# LPDDR4X_Ground.net
KiCad netlist of a schematic drawn in Altium Designer
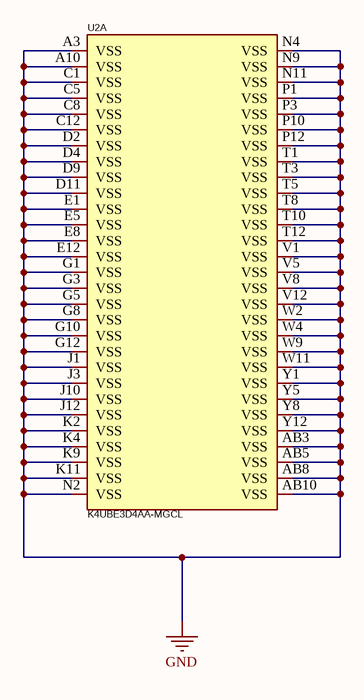
[diagram p0: LPDDR4X_Ground.SchDoc]

(export (version "E")
  (design (tool "Eeschema 10.0.6"))
  (components
    (comp (ref "U2")
      (value "K4UBE3D4AA-MGCL")
      (footprint "K4F8E304HB-MGCJ")
      (fields (field (name "MANUFACTURER") "SAMSUNG(三星半导体)"))
      (libsource (lib "kit") (part "K4UBE3D4AA-MGCL"))
    )
  )
  (nets
    (net (code "1") (name "GND") (class "Default")
      (node (ref "U2") (pin "A10") (pinfunction "VSS_A10") (pintype "passive"))
      (node (ref "U2") (pin "A3") (pinfunction "VSS_A3") (pintype "passive"))
      (node (ref "U2") (pin "AB10") (pinfunction "VSS_AB10") (pintype "passive"))
      (node (ref "U2") (pin "AB3") (pinfunction "VSS_AB3") (pintype "passive"))
      (node (ref "U2") (pin "AB5") (pinfunction "VSS_AB5") (pintype "passive"))
      (node (ref "U2") (pin "AB8") (pinfunction "VSS_AB8") (pintype "passive"))
      (node (ref "U2") (pin "C1") (pinfunction "VSS_C1") (pintype "passive"))
      (node (ref "U2") (pin "C12") (pinfunction "VSS_C12") (pintype "passive"))
      (node (ref "U2") (pin "C5") (pinfunction "VSS_C5") (pintype "passive"))
      (node (ref "U2") (pin "C8") (pinfunction "VSS_C8") (pintype "passive"))
      (node (ref "U2") (pin "D11") (pinfunction "VSS_D11") (pintype "passive"))
      (node (ref "U2") (pin "D2") (pinfunction "VSS_D2") (pintype "passive"))
      (node (ref "U2") (pin "D4") (pinfunction "VSS_D4") (pintype "passive"))
      (node (ref "U2") (pin "D9") (pinfunction "VSS_D9") (pintype "passive"))
      (node (ref "U2") (pin "E1") (pinfunction "VSS_E1") (pintype "passive"))
      (node (ref "U2") (pin "E12") (pinfunction "VSS_E12") (pintype "passive"))
      (node (ref "U2") (pin "E5") (pinfunction "VSS_E5") (pintype "passive"))
      (node (ref "U2") (pin "E8") (pinfunction "VSS_E8") (pintype "passive"))
      (node (ref "U2") (pin "G1") (pinfunction "VSS_G1") (pintype "passive"))
      (node (ref "U2") (pin "G10") (pinfunction "VSS_G10") (pintype "passive"))
      (node (ref "U2") (pin "G12") (pinfunction "VSS_G12") (pintype "passive"))
      (node (ref "U2") (pin "G3") (pinfunction "VSS_G3") (pintype "passive"))
      (node (ref "U2") (pin "G5") (pinfunction "VSS_G5") (pintype "passive"))
      (node (ref "U2") (pin "G8") (pinfunction "VSS_G8") (pintype "passive"))
      (node (ref "U2") (pin "J1") (pinfunction "VSS_J1") (pintype "passive"))
      (node (ref "U2") (pin "J10") (pinfunction "VSS_J10") (pintype "passive"))
      (node (ref "U2") (pin "J12") (pinfunction "VSS_J12") (pintype "passive"))
      (node (ref "U2") (pin "J3") (pinfunction "VSS_J3") (pintype "passive"))
      (node (ref "U2") (pin "K11") (pinfunction "VSS_K11") (pintype "passive"))
      (node (ref "U2") (pin "K2") (pinfunction "VSS_K2") (pintype "passive"))
      (node (ref "U2") (pin "K4") (pinfunction "VSS_K4") (pintype "passive"))
      (node (ref "U2") (pin "K9") (pinfunction "VSS_K9") (pintype "passive"))
      (node (ref "U2") (pin "N11") (pinfunction "VSS_N11") (pintype "passive"))
      (node (ref "U2") (pin "N2") (pinfunction "VSS_N2") (pintype "passive"))
      (node (ref "U2") (pin "N4") (pinfunction "VSS_N4") (pintype "passive"))
      (node (ref "U2") (pin "N9") (pinfunction "VSS_N9") (pintype "passive"))
      (node (ref "U2") (pin "P1") (pinfunction "VSS_P1") (pintype "passive"))
      (node (ref "U2") (pin "P10") (pinfunction "VSS_P10") (pintype "passive"))
      (node (ref "U2") (pin "P12") (pinfunction "VSS_P12") (pintype "passive"))
      (node (ref "U2") (pin "P3") (pinfunction "VSS_P3") (pintype "passive"))
      (node (ref "U2") (pin "T1") (pinfunction "VSS_T1") (pintype "passive"))
      (node (ref "U2") (pin "T10") (pinfunction "VSS_T10") (pintype "passive"))
      (node (ref "U2") (pin "T12") (pinfunction "VSS_T12") (pintype "passive"))
      (node (ref "U2") (pin "T3") (pinfunction "VSS_T3") (pintype "passive"))
      (node (ref "U2") (pin "T5") (pinfunction "VSS_T5") (pintype "passive"))
      (node (ref "U2") (pin "T8") (pinfunction "VSS_T8") (pintype "passive"))
      (node (ref "U2") (pin "V1") (pinfunction "VSS_V1") (pintype "passive"))
      (node (ref "U2") (pin "V12") (pinfunction "VSS_V12") (pintype "passive"))
      (node (ref "U2") (pin "V5") (pinfunction "VSS_V5") (pintype "passive"))
      (node (ref "U2") (pin "V8") (pinfunction "VSS_V8") (pintype "passive"))
      (node (ref "U2") (pin "W11") (pinfunction "VSS_W11") (pintype "passive"))
      (node (ref "U2") (pin "W2") (pinfunction "VSS_W2") (pintype "passive"))
      (node (ref "U2") (pin "W4") (pinfunction "VSS_W4") (pintype "passive"))
      (node (ref "U2") (pin "W9") (pinfunction "VSS_W9") (pintype "passive"))
      (node (ref "U2") (pin "Y1") (pinfunction "VSS_Y1") (pintype "passive"))
      (node (ref "U2") (pin "Y12") (pinfunction "VSS_Y12") (pintype "passive"))
      (node (ref "U2") (pin "Y5") (pinfunction "VSS_Y5") (pintype "passive"))
      (node (ref "U2") (pin "Y8") (pinfunction "VSS_Y8") (pintype "passive"))
    )
  )
)
